# wireless-dong-mk-2_1.net
KiCad netlist of a schematic drawn in EAGLE
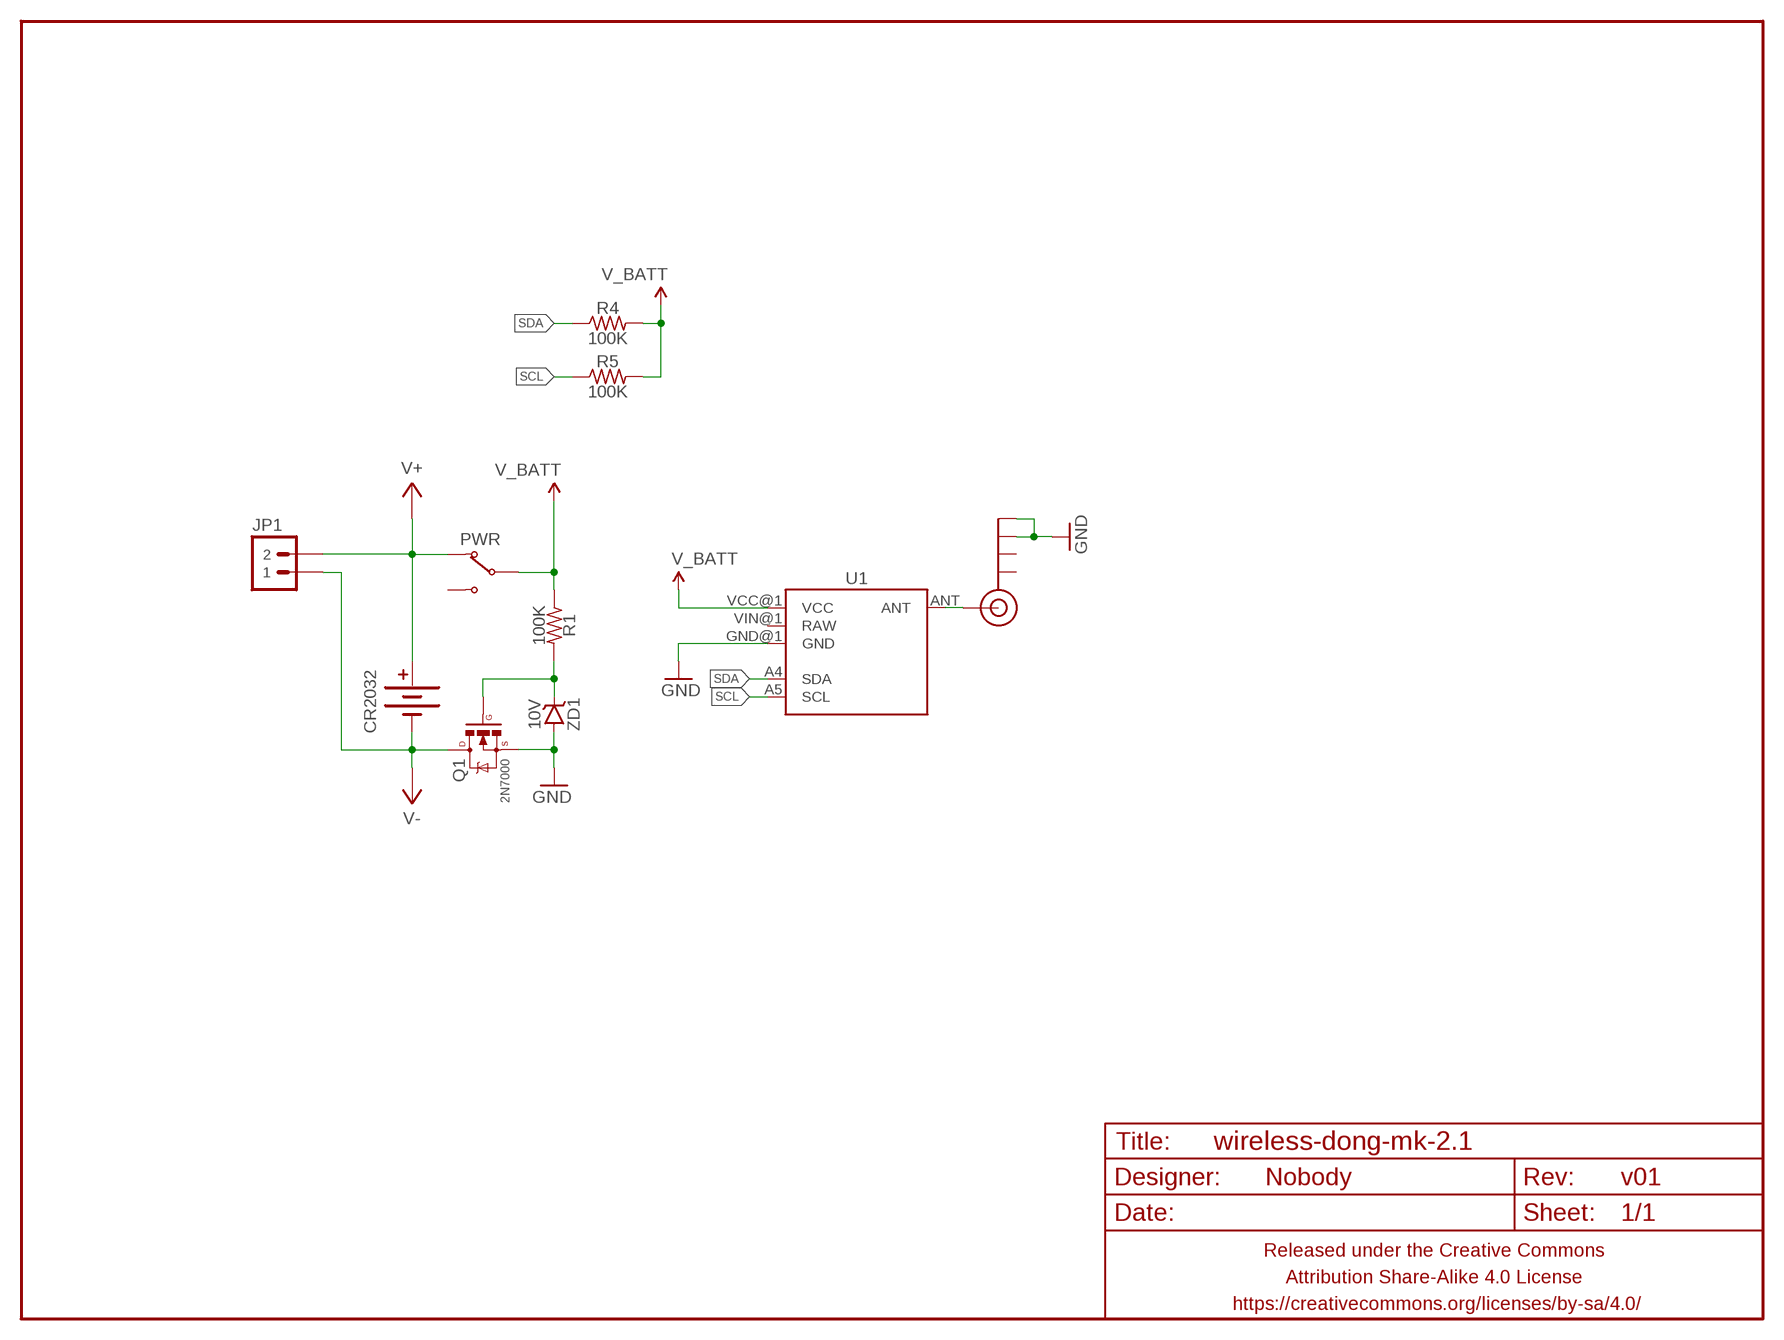
[diagram p0: schematic, sheet 1]

(export (version "E")
  (design (tool "Eeschema 10.0.6"))
  (components
    (comp (ref "ANT")
      (value "SMA_EDGE")
      (footprint "eagle-import:SMA-EDGE")
      (libsource (lib "eagle-import") (part "SMA_EDGE"))
    )
    (comp (ref "CR2032")
      (value "BATTERY20PTH_TOPLOAD")
      (footprint "eagle-import:BATTCON_20MM_PTH_TOPLOAD")
      (libsource (lib "eagle-import") (part "BATTERY20PTH_TOPLOAD"))
    )
    (comp (ref "FRAME1")
      (value "FRAME-LETTERNO_PACKAGE")
      (footprint "eagle-import:DUMMY")
      (fields (field (name "DESIGNER") "Nobody"))
      (libsource (lib "eagle-import") (part "FRAME-LETTERNO_PACKAGE"))
    )
    (comp (ref "JP1")
      (value "M02PTH-CENTERED-R+")
      (footprint "eagle-import:1X02-CENTER-R+")
      (libsource (lib "eagle-import") (part "M02PTH-CENTERED-R+"))
    )
    (comp (ref "PWR")
      (value "SWITCH-SPDTPTH-RA-2.54MM")
      (footprint "eagle-import:SPDT-RA-2.54MM")
      (libsource (lib "eagle-import") (part "SWITCH-SPDTPTH-RA-2.54MM"))
    )
    (comp (ref "Q1")
      (value "2N7000")
      (footprint "eagle-import:SOT23")
      (libsource (lib "eagle-import") (part "MOSFET-NCHANNELIRLML2502"))
    )
    (comp (ref "R1")
      (value "100K")
      (footprint "eagle-import:R0603")
      (libsource (lib "eagle-import") (part "RESISTORR0603"))
    )
    (comp (ref "R4")
      (value "100K")
      (footprint "eagle-import:R0603")
      (libsource (lib "eagle-import") (part "RESISTORR0603"))
    )
    (comp (ref "R5")
      (value "100K")
      (footprint "eagle-import:R0603")
      (libsource (lib "eagle-import") (part "RESISTORR0603"))
    )
    (comp (ref "U1")
      (value "MOTEINO_BOAT")
      (footprint "eagle-import:MOTEINO_BOAT")
      (libsource (lib "eagle-import") (part "MOTEINO_BOAT"))
    )
    (comp (ref "ZD1")
      (value "10V")
      (footprint "eagle-import:SOT23")
      (libsource (lib "eagle-import") (part "DIODE-ZENERSOT23"))
    )
  )
  (nets
    (net (code "1") (name "GND") (class "Default")
      (node (ref "ANT") (pin "GND@2") (pinfunction "GND_GND@2") (pintype "bidirectional"))
      (node (ref "ANT") (pin "GND@3") (pinfunction "GND_GND@3") (pintype "bidirectional"))
      (node (ref "Q1") (pin "2") (pinfunction "S_2") (pintype "passive"))
      (node (ref "U1") (pin "GND@1") (pinfunction "GND_GND@1") (pintype "bidirectional"))
      (node (ref "ZD1") (pin "1") (pinfunction "A_1") (pintype "passive"))
      (node (ref "ZD1") (pin "2") (pinfunction "A_2") (pintype "passive"))
    )
    (net (code "2") (name "Net-(ANT-SIGNAL)") (class "Default")
      (node (ref "ANT") (pin "SIG") (pinfunction "SIGNAL_SIG") (pintype "bidirectional"))
      (node (ref "U1") (pin "ANT") (pinfunction "ANT_ANT") (pintype "bidirectional"))
    )
    (net (code "3") (name "Net-(Q1-G)") (class "Default")
      (node (ref "Q1") (pin "1") (pinfunction "G_1") (pintype "passive"))
      (node (ref "R1") (pin "2") (pinfunction "2_2") (pintype "passive"))
      (node (ref "ZD1") (pin "3") (pinfunction "C_3") (pintype "passive"))
    )
    (net (code "4") (name "SCL") (class "Default")
      (node (ref "R5") (pin "1") (pinfunction "1_1") (pintype "passive"))
      (node (ref "U1") (pin "A5") (pinfunction "SCL_A5") (pintype "bidirectional"))
    )
    (net (code "5") (name "SDA") (class "Default")
      (node (ref "R4") (pin "1") (pinfunction "1_1") (pintype "passive"))
      (node (ref "U1") (pin "A4") (pinfunction "SDA_A4") (pintype "bidirectional"))
    )
    (net (code "6") (name "V+") (class "Default")
      (node (ref "CR2032") (pin "+") (pinfunction "+_+") (pintype "power_in"))
      (node (ref "JP1") (pin "2") (pinfunction "2_2") (pintype "passive"))
      (node (ref "PWR") (pin "1") (pinfunction "NC_1") (pintype "passive"))
    )
    (net (code "7") (name "V-") (class "Default")
      (node (ref "CR2032") (pin "-") (pinfunction "-_-") (pintype "power_in"))
      (node (ref "JP1") (pin "1") (pinfunction "1_1") (pintype "passive"))
      (node (ref "Q1") (pin "3") (pinfunction "D_3") (pintype "passive"))
    )
    (net (code "8") (name "V_BATT") (class "Default")
      (node (ref "PWR") (pin "2") (pinfunction "COM_2") (pintype "passive"))
      (node (ref "R1") (pin "1") (pinfunction "1_1") (pintype "passive"))
      (node (ref "R4") (pin "2") (pinfunction "2_2") (pintype "passive"))
      (node (ref "R5") (pin "2") (pinfunction "2_2") (pintype "passive"))
      (node (ref "U1") (pin "VCC@1") (pinfunction "VCC_VCC@1") (pintype "bidirectional"))
    )
    (net (code "9") (name "unconnected-(ANT-GND-PadGND@0)") (class "Default")
      (node (ref "ANT") (pin "GND@0") (pinfunction "GND_GND@0") (pintype "bidirectional"))
    )
    (net (code "10") (name "unconnected-(ANT-GND-PadGND@1)") (class "Default")
      (node (ref "ANT") (pin "GND@1") (pinfunction "GND_GND@1") (pintype "bidirectional"))
    )
    (net (code "11") (name "unconnected-(PWR-NO-Pad3)") (class "Default")
      (node (ref "PWR") (pin "3") (pinfunction "NO_3") (pintype "passive"))
    )
    (net (code "12") (name "unconnected-(U1-RAW-PadVIN@1)") (class "Default")
      (node (ref "U1") (pin "VIN@1") (pinfunction "RAW_VIN@1") (pintype "bidirectional"))
    )
  )
)
